# Digital.net
KiCad netlist of a schematic drawn in Altium Designer
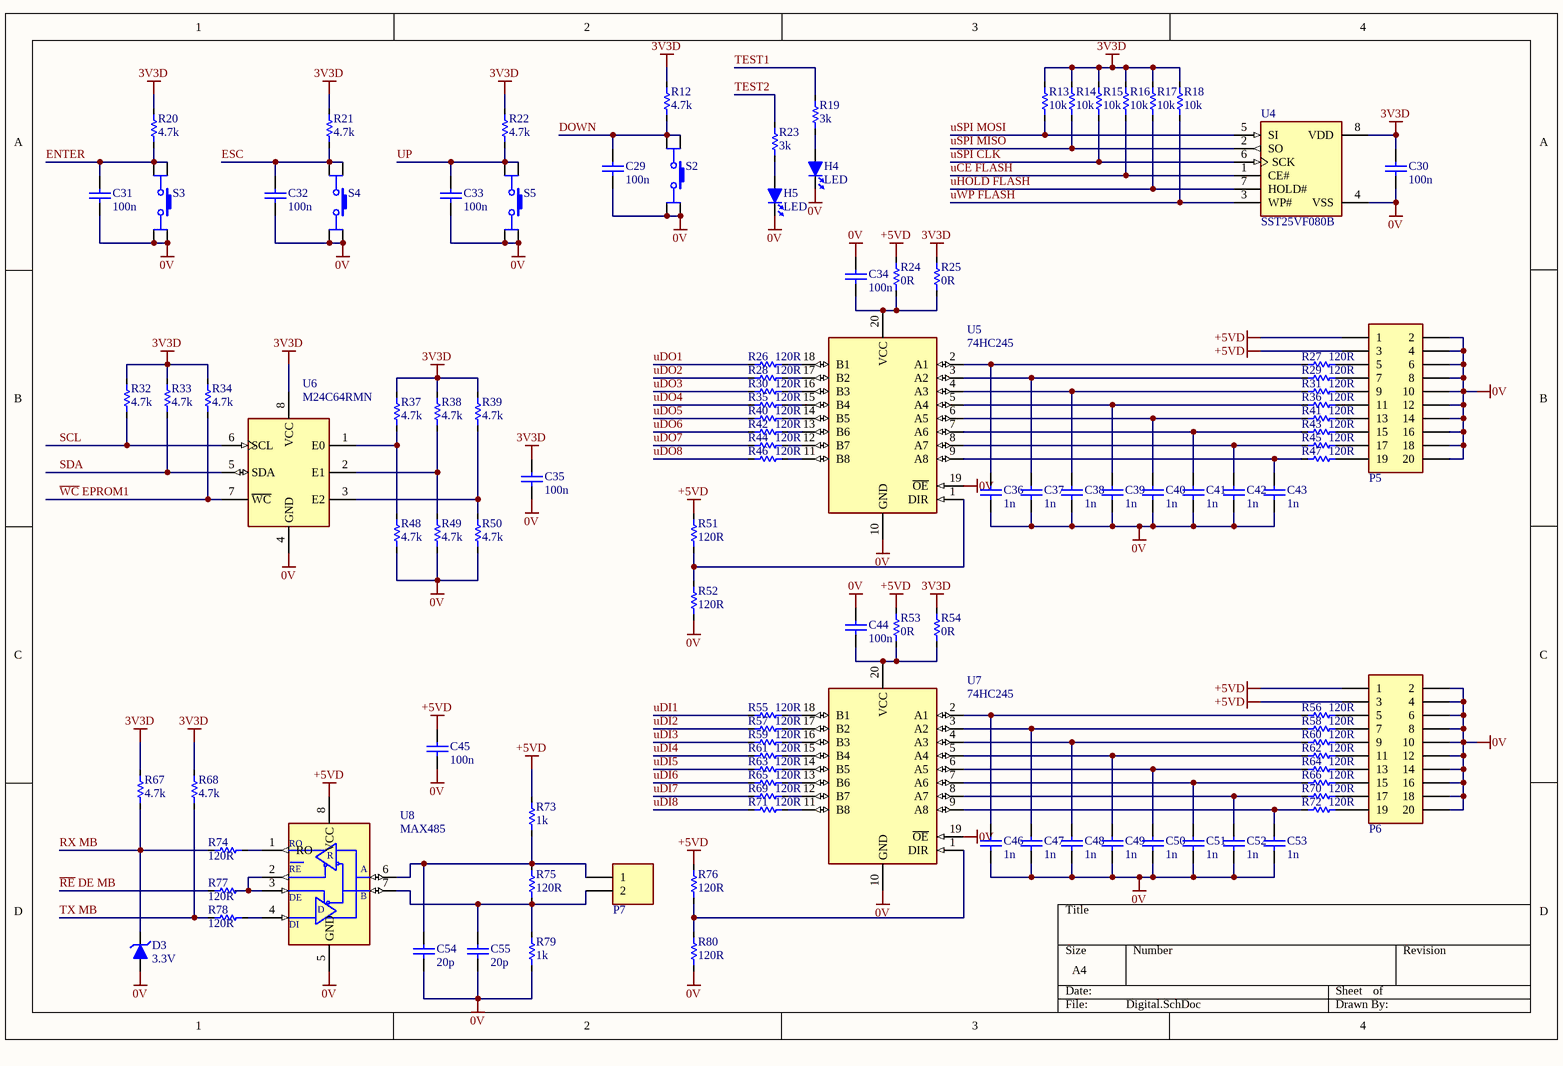
[diagram p0: Digital.SchDoc]

(export (version "E")
  (design (tool "Eeschema 10.0.6"))
  (components
    (comp (ref "C29")
      (value "100n")
      (footprint "CC3216-1206L")
      (description "Capacitor")
      (libsource (lib "SchLibrary") (part "CAPACITOR NON-POL"))
    )
    (comp (ref "C30")
      (value "100n")
      (footprint "CC3216-1206L")
      (description "Capacitor")
      (libsource (lib "SchLibrary") (part "CAPACITOR NON-POL"))
    )
    (comp (ref "C31")
      (value "100n")
      (footprint "CC3216-1206L")
      (description "Capacitor")
      (libsource (lib "SchLibrary") (part "CAPACITOR NON-POL"))
    )
    (comp (ref "C32")
      (value "100n")
      (footprint "CC3216-1206L")
      (description "Capacitor")
      (libsource (lib "SchLibrary") (part "CAPACITOR NON-POL"))
    )
    (comp (ref "C33")
      (value "100n")
      (footprint "CC3216-1206L")
      (description "Capacitor")
      (libsource (lib "SchLibrary") (part "CAPACITOR NON-POL"))
    )
    (comp (ref "C34")
      (value "100n")
      (footprint "CC3216-1206L")
      (description "Capacitor")
      (libsource (lib "SchLibrary") (part "CAPACITOR NON-POL"))
    )
    (comp (ref "C35")
      (value "100n")
      (footprint "CC3216-1206L")
      (description "Capacitor")
      (libsource (lib "SchLibrary") (part "CAPACITOR NON-POL"))
    )
    (comp (ref "C36")
      (value "1n")
      (footprint "CC3216-1206L")
      (description "Capacitor")
      (libsource (lib "SchLibrary") (part "CAPACITOR NON-POL"))
    )
    (comp (ref "C37")
      (value "1n")
      (footprint "CC3216-1206L")
      (description "Capacitor")
      (libsource (lib "SchLibrary") (part "CAPACITOR NON-POL"))
    )
    (comp (ref "C38")
      (value "1n")
      (footprint "CC3216-1206L")
      (description "Capacitor")
      (libsource (lib "SchLibrary") (part "CAPACITOR NON-POL"))
    )
    (comp (ref "C39")
      (value "1n")
      (footprint "CC3216-1206L")
      (description "Capacitor")
      (libsource (lib "SchLibrary") (part "CAPACITOR NON-POL"))
    )
    (comp (ref "C40")
      (value "1n")
      (footprint "CC3216-1206L")
      (description "Capacitor")
      (libsource (lib "SchLibrary") (part "CAPACITOR NON-POL"))
    )
    (comp (ref "C41")
      (value "1n")
      (footprint "CC3216-1206L")
      (description "Capacitor")
      (libsource (lib "SchLibrary") (part "CAPACITOR NON-POL"))
    )
    (comp (ref "C42")
      (value "1n")
      (footprint "CC3216-1206L")
      (description "Capacitor")
      (libsource (lib "SchLibrary") (part "CAPACITOR NON-POL"))
    )
    (comp (ref "C43")
      (value "1n")
      (footprint "CC3216-1206L")
      (description "Capacitor")
      (libsource (lib "SchLibrary") (part "CAPACITOR NON-POL"))
    )
    (comp (ref "C44")
      (value "100n")
      (footprint "CC3216-1206L")
      (description "Capacitor")
      (libsource (lib "SchLibrary") (part "CAPACITOR NON-POL"))
    )
    (comp (ref "C45")
      (value "100n")
      (footprint "CC3216-1206L")
      (description "Capacitor")
      (libsource (lib "SchLibrary") (part "CAPACITOR NON-POL"))
    )
    (comp (ref "C46")
      (value "1n")
      (footprint "CC3216-1206L")
      (description "Capacitor")
      (libsource (lib "SchLibrary") (part "CAPACITOR NON-POL"))
    )
    (comp (ref "C47")
      (value "1n")
      (footprint "CC3216-1206L")
      (description "Capacitor")
      (libsource (lib "SchLibrary") (part "CAPACITOR NON-POL"))
    )
    (comp (ref "C48")
      (value "1n")
      (footprint "CC3216-1206L")
      (description "Capacitor")
      (libsource (lib "SchLibrary") (part "CAPACITOR NON-POL"))
    )
    (comp (ref "C49")
      (value "1n")
      (footprint "CC3216-1206L")
      (description "Capacitor")
      (libsource (lib "SchLibrary") (part "CAPACITOR NON-POL"))
    )
    (comp (ref "C50")
      (value "1n")
      (footprint "CC3216-1206L")
      (description "Capacitor")
      (libsource (lib "SchLibrary") (part "CAPACITOR NON-POL"))
    )
    (comp (ref "C51")
      (value "1n")
      (footprint "CC3216-1206L")
      (description "Capacitor")
      (libsource (lib "SchLibrary") (part "CAPACITOR NON-POL"))
    )
    (comp (ref "C52")
      (value "1n")
      (footprint "CC3216-1206L")
      (description "Capacitor")
      (libsource (lib "SchLibrary") (part "CAPACITOR NON-POL"))
    )
    (comp (ref "C53")
      (value "1n")
      (footprint "CC3216-1206L")
      (description "Capacitor")
      (libsource (lib "SchLibrary") (part "CAPACITOR NON-POL"))
    )
    (comp (ref "C54")
      (value "20p")
      (footprint "CC3216-1206L")
      (description "Capacitor")
      (libsource (lib "SchLibrary") (part "CAPACITOR NON-POL"))
    )
    (comp (ref "C55")
      (value "20p")
      (footprint "CC3216-1206L")
      (description "Capacitor")
      (libsource (lib "SchLibrary") (part "CAPACITOR NON-POL"))
    )
    (comp (ref "D3")
      (value "3.3V")
      (footprint "SOD123")
      (description "DIODE ZENER")
      (libsource (lib "SchLibrary") (part "DIODE ZENER"))
    )
    (comp (ref "H4") (value "LED") (footprint "LED1206") (libsource (lib "SchLibrary") (part "LED")))
    (comp (ref "H5") (value "LED") (footprint "LED1206") (libsource (lib "SchLibrary") (part "LED")))
    (comp (ref "P5")
      (value "CONNECTOR, 2x10, 20P")
      (footprint "HDR_MALE_2X10_20P_2.54MM_180")
      (libsource (lib "SchLibrary") (part "CONNECTOR, 2x10, 20P"))
    )
    (comp (ref "P6")
      (value "CONNECTOR, 2x10, 20P")
      (footprint "HDR_MALE_2X10_20P_2.54MM_180")
      (libsource (lib "SchLibrary") (part "CONNECTOR, 2x10, 20P"))
    )
    (comp (ref "P7")
      (value "CONNECTOR, 1x2, 2P")
      (footprint "DS1070-2MVV6")
      (libsource (lib "SchLibrary") (part "CONNECTOR, 1x2, 2P"))
    )
    (comp (ref "R12")
      (value "4.7k")
      (footprint "CR3216-1206l")
      (description "Resistor")
      (libsource (lib "SchLibrary") (part "RESISTOR"))
    )
    (comp (ref "R13")
      (value "10k")
      (footprint "CR3216-1206l")
      (description "Resistor")
      (libsource (lib "SchLibrary") (part "RESISTOR"))
    )
    (comp (ref "R14")
      (value "10k")
      (footprint "CR3216-1206l")
      (description "Resistor")
      (libsource (lib "SchLibrary") (part "RESISTOR"))
    )
    (comp (ref "R15")
      (value "10k")
      (footprint "CR3216-1206l")
      (description "Resistor")
      (libsource (lib "SchLibrary") (part "RESISTOR"))
    )
    (comp (ref "R16")
      (value "10k")
      (footprint "CR3216-1206l")
      (description "Resistor")
      (libsource (lib "SchLibrary") (part "RESISTOR"))
    )
    (comp (ref "R17")
      (value "10k")
      (footprint "CR3216-1206l")
      (description "Resistor")
      (libsource (lib "SchLibrary") (part "RESISTOR"))
    )
    (comp (ref "R18")
      (value "10k")
      (footprint "CR3216-1206l")
      (description "Resistor")
      (libsource (lib "SchLibrary") (part "RESISTOR"))
    )
    (comp (ref "R19")
      (value "3k")
      (footprint "CR3216-1206l")
      (description "Resistor")
      (libsource (lib "SchLibrary") (part "RESISTOR"))
    )
    (comp (ref "R20")
      (value "4.7k")
      (footprint "CR3216-1206l")
      (description "Resistor")
      (libsource (lib "SchLibrary") (part "RESISTOR"))
    )
    (comp (ref "R21")
      (value "4.7k")
      (footprint "CR3216-1206l")
      (description "Resistor")
      (libsource (lib "SchLibrary") (part "RESISTOR"))
    )
    (comp (ref "R22")
      (value "4.7k")
      (footprint "CR3216-1206l")
      (description "Resistor")
      (libsource (lib "SchLibrary") (part "RESISTOR"))
    )
    (comp (ref "R23")
      (value "3k")
      (footprint "CR3216-1206l")
      (description "Resistor")
      (libsource (lib "SchLibrary") (part "RESISTOR"))
    )
    (comp (ref "R24")
      (value "0R")
      (footprint "CR3216-1206l")
      (description "Resistor")
      (libsource (lib "SchLibrary") (part "RESISTOR"))
    )
    (comp (ref "R25")
      (value "0R")
      (footprint "CR3216-1206l")
      (description "Resistor")
      (libsource (lib "SchLibrary") (part "RESISTOR"))
    )
    (comp (ref "R26")
      (value "120R")
      (footprint "CR3216-1206l")
      (description "Resistor")
      (libsource (lib "SchLibrary") (part "RESISTOR"))
    )
    (comp (ref "R27")
      (value "120R")
      (footprint "CR3216-1206l")
      (description "Resistor")
      (libsource (lib "SchLibrary") (part "RESISTOR"))
    )
    (comp (ref "R28")
      (value "120R")
      (footprint "CR3216-1206l")
      (description "Resistor")
      (libsource (lib "SchLibrary") (part "RESISTOR"))
    )
    (comp (ref "R29")
      (value "120R")
      (footprint "CR3216-1206l")
      (description "Resistor")
      (libsource (lib "SchLibrary") (part "RESISTOR"))
    )
    (comp (ref "R30")
      (value "120R")
      (footprint "CR3216-1206l")
      (description "Resistor")
      (libsource (lib "SchLibrary") (part "RESISTOR"))
    )
    (comp (ref "R31")
      (value "120R")
      (footprint "CR3216-1206l")
      (description "Resistor")
      (libsource (lib "SchLibrary") (part "RESISTOR"))
    )
    (comp (ref "R32")
      (value "4.7k")
      (footprint "CR3216-1206l")
      (description "Resistor")
      (libsource (lib "SchLibrary") (part "RESISTOR"))
    )
    (comp (ref "R33")
      (value "4.7k")
      (footprint "CR3216-1206l")
      (description "Resistor")
      (libsource (lib "SchLibrary") (part "RESISTOR"))
    )
    (comp (ref "R34")
      (value "4.7k")
      (footprint "CR3216-1206l")
      (description "Resistor")
      (libsource (lib "SchLibrary") (part "RESISTOR"))
    )
    (comp (ref "R35")
      (value "120R")
      (footprint "CR3216-1206l")
      (description "Resistor")
      (libsource (lib "SchLibrary") (part "RESISTOR"))
    )
    (comp (ref "R36")
      (value "120R")
      (footprint "CR3216-1206l")
      (description "Resistor")
      (libsource (lib "SchLibrary") (part "RESISTOR"))
    )
    (comp (ref "R37")
      (value "4.7k")
      (footprint "CR3216-1206l")
      (description "Resistor")
      (libsource (lib "SchLibrary") (part "RESISTOR"))
    )
    (comp (ref "R38")
      (value "4.7k")
      (footprint "CR3216-1206l")
      (description "Resistor")
      (libsource (lib "SchLibrary") (part "RESISTOR"))
    )
    (comp (ref "R39")
      (value "4.7k")
      (footprint "CR3216-1206l")
      (description "Resistor")
      (libsource (lib "SchLibrary") (part "RESISTOR"))
    )
    (comp (ref "R40")
      (value "120R")
      (footprint "CR3216-1206l")
      (description "Resistor")
      (libsource (lib "SchLibrary") (part "RESISTOR"))
    )
    (comp (ref "R41")
      (value "120R")
      (footprint "CR3216-1206l")
      (description "Resistor")
      (libsource (lib "SchLibrary") (part "RESISTOR"))
    )
    (comp (ref "R42")
      (value "120R")
      (footprint "CR3216-1206l")
      (description "Resistor")
      (libsource (lib "SchLibrary") (part "RESISTOR"))
    )
    (comp (ref "R43")
      (value "120R")
      (footprint "CR3216-1206l")
      (description "Resistor")
      (libsource (lib "SchLibrary") (part "RESISTOR"))
    )
    (comp (ref "R44")
      (value "120R")
      (footprint "CR3216-1206l")
      (description "Resistor")
      (libsource (lib "SchLibrary") (part "RESISTOR"))
    )
    (comp (ref "R45")
      (value "120R")
      (footprint "CR3216-1206l")
      (description "Resistor")
      (libsource (lib "SchLibrary") (part "RESISTOR"))
    )
    (comp (ref "R46")
      (value "120R")
      (footprint "CR3216-1206l")
      (description "Resistor")
      (libsource (lib "SchLibrary") (part "RESISTOR"))
    )
    (comp (ref "R47")
      (value "120R")
      (footprint "CR3216-1206l")
      (description "Resistor")
      (libsource (lib "SchLibrary") (part "RESISTOR"))
    )
    (comp (ref "R48")
      (value "4.7k")
      (footprint "CR3216-1206l")
      (description "Resistor")
      (libsource (lib "SchLibrary") (part "RESISTOR"))
    )
    (comp (ref "R49")
      (value "4.7k")
      (footprint "CR3216-1206l")
      (description "Resistor")
      (libsource (lib "SchLibrary") (part "RESISTOR"))
    )
    (comp (ref "R50")
      (value "4.7k")
      (footprint "CR3216-1206l")
      (description "Resistor")
      (libsource (lib "SchLibrary") (part "RESISTOR"))
    )
    (comp (ref "R51")
      (value "120R")
      (footprint "CR3216-1206l")
      (description "Resistor")
      (libsource (lib "SchLibrary") (part "RESISTOR"))
    )
    (comp (ref "R52")
      (value "120R")
      (footprint "CR3216-1206l")
      (description "Resistor")
      (libsource (lib "SchLibrary") (part "RESISTOR"))
    )
    (comp (ref "R53")
      (value "0R")
      (footprint "CR3216-1206l")
      (description "Resistor")
      (libsource (lib "SchLibrary") (part "RESISTOR"))
    )
    (comp (ref "R54")
      (value "0R")
      (footprint "CR3216-1206l")
      (description "Resistor")
      (libsource (lib "SchLibrary") (part "RESISTOR"))
    )
    (comp (ref "R55")
      (value "120R")
      (footprint "CR3216-1206l")
      (description "Resistor")
      (libsource (lib "SchLibrary") (part "RESISTOR"))
    )
    (comp (ref "R56")
      (value "120R")
      (footprint "CR3216-1206l")
      (description "Resistor")
      (libsource (lib "SchLibrary") (part "RESISTOR"))
    )
    (comp (ref "R57")
      (value "120R")
      (footprint "CR3216-1206l")
      (description "Resistor")
      (libsource (lib "SchLibrary") (part "RESISTOR"))
    )
    (comp (ref "R58")
      (value "120R")
      (footprint "CR3216-1206l")
      (description "Resistor")
      (libsource (lib "SchLibrary") (part "RESISTOR"))
    )
    (comp (ref "R59")
      (value "120R")
      (footprint "CR3216-1206l")
      (description "Resistor")
      (libsource (lib "SchLibrary") (part "RESISTOR"))
    )
    (comp (ref "R60")
      (value "120R")
      (footprint "CR3216-1206l")
      (description "Resistor")
      (libsource (lib "SchLibrary") (part "RESISTOR"))
    )
    (comp (ref "R61")
      (value "120R")
      (footprint "CR3216-1206l")
      (description "Resistor")
      (libsource (lib "SchLibrary") (part "RESISTOR"))
    )
    (comp (ref "R62")
      (value "120R")
      (footprint "CR3216-1206l")
      (description "Resistor")
      (libsource (lib "SchLibrary") (part "RESISTOR"))
    )
    (comp (ref "R63")
      (value "120R")
      (footprint "CR3216-1206l")
      (description "Resistor")
      (libsource (lib "SchLibrary") (part "RESISTOR"))
    )
    (comp (ref "R64")
      (value "120R")
      (footprint "CR3216-1206l")
      (description "Resistor")
      (libsource (lib "SchLibrary") (part "RESISTOR"))
    )
    (comp (ref "R65")
      (value "120R")
      (footprint "CR3216-1206l")
      (description "Resistor")
      (libsource (lib "SchLibrary") (part "RESISTOR"))
    )
    (comp (ref "R66")
      (value "120R")
      (footprint "CR3216-1206l")
      (description "Resistor")
      (libsource (lib "SchLibrary") (part "RESISTOR"))
    )
    (comp (ref "R67")
      (value "4.7k")
      (footprint "CR3216-1206l")
      (description "Resistor")
      (libsource (lib "SchLibrary") (part "RESISTOR"))
    )
    (comp (ref "R68")
      (value "4.7k")
      (footprint "CR3216-1206l")
      (description "Resistor")
      (libsource (lib "SchLibrary") (part "RESISTOR"))
    )
    (comp (ref "R69")
      (value "120R")
      (footprint "CR3216-1206l")
      (description "Resistor")
      (libsource (lib "SchLibrary") (part "RESISTOR"))
    )
    (comp (ref "R70")
      (value "120R")
      (footprint "CR3216-1206l")
      (description "Resistor")
      (libsource (lib "SchLibrary") (part "RESISTOR"))
    )
    (comp (ref "R71")
      (value "120R")
      (footprint "CR3216-1206l")
      (description "Resistor")
      (libsource (lib "SchLibrary") (part "RESISTOR"))
    )
    (comp (ref "R72")
      (value "120R")
      (footprint "CR3216-1206l")
      (description "Resistor")
      (libsource (lib "SchLibrary") (part "RESISTOR"))
    )
    (comp (ref "R73")
      (value "1k")
      (footprint "CR3216-1206l")
      (description "Resistor")
      (libsource (lib "SchLibrary") (part "RESISTOR"))
    )
    (comp (ref "R74")
      (value "120R")
      (footprint "CR3216-1206l")
      (description "Resistor")
      (libsource (lib "SchLibrary") (part "RESISTOR"))
    )
    (comp (ref "R75")
      (value "120R")
      (footprint "CR3216-1206l")
      (description "Resistor")
      (libsource (lib "SchLibrary") (part "RESISTOR"))
    )
    (comp (ref "R76")
      (value "120R")
      (footprint "CR3216-1206l")
      (description "Resistor")
      (libsource (lib "SchLibrary") (part "RESISTOR"))
    )
    (comp (ref "R77")
      (value "120R")
      (footprint "CR3216-1206l")
      (description "Resistor")
      (libsource (lib "SchLibrary") (part "RESISTOR"))
    )
    (comp (ref "R78")
      (value "120R")
      (footprint "CR3216-1206l")
      (description "Resistor")
      (libsource (lib "SchLibrary") (part "RESISTOR"))
    )
    (comp (ref "R79")
      (value "1k")
      (footprint "CR3216-1206l")
      (description "Resistor")
      (libsource (lib "SchLibrary") (part "RESISTOR"))
    )
    (comp (ref "R80")
      (value "120R")
      (footprint "CR3216-1206l")
      (description "Resistor")
      (libsource (lib "SchLibrary") (part "RESISTOR"))
    )
    (comp (ref "S2")
      (value "SWITCH TACT")
      (footprint "SWITCH TACTILE SMD 6x6 4.3mm")
      (description "TACT SWITCH")
      (libsource (lib "SchLibrary") (part "SWITCH TACT"))
    )
    (comp (ref "S3")
      (value "SWITCH TACT")
      (footprint "SWITCH TACTILE SMD 6x6 4.3mm")
      (description "TACT SWITCH")
      (libsource (lib "SchLibrary") (part "SWITCH TACT"))
    )
    (comp (ref "S4")
      (value "SWITCH TACT")
      (footprint "SWITCH TACTILE SMD 6x6 4.3mm")
      (description "TACT SWITCH")
      (libsource (lib "SchLibrary") (part "SWITCH TACT"))
    )
    (comp (ref "S5")
      (value "SWITCH TACT")
      (footprint "SWITCH TACTILE SMD 6x6 4.3mm")
      (description "TACT SWITCH")
      (libsource (lib "SchLibrary") (part "SWITCH TACT"))
    )
    (comp (ref "U4")
      (value "SST25VF080B")
      (footprint "SOIC08-S2A")
      (libsource (lib "SchLibrary") (part "SST25VF080B"))
    )
    (comp (ref "U5")
      (value "74HC245")
      (footprint "SOIC127P1030X265-20M")
      (description "IC BUS TRANSCEIVER 8BIT 20-Pin")
      (libsource (lib "SchLibrary") (part "74HC245"))
    )
    (comp (ref "U6")
      (value "M24C64RMN")
      (footprint "SOIC127P600X175-8N")
      (libsource (lib "SchLibrary") (part "M24C64RMN"))
    )
    (comp (ref "U7")
      (value "74HC245")
      (footprint "SOIC127P1030X265-20M")
      (description "IC BUS TRANSCEIVER 8BIT 20-Pin")
      (libsource (lib "SchLibrary") (part "74HC245"))
    )
    (comp (ref "U8")
      (value "MAX485")
      (footprint "SOIC127P600X175-8N")
      (description "ROHS-ICMAX485CSA MAXIM")
      (libsource (lib "SchLibrary") (part "MAX485"))
    )
  )
  (nets
    (net (code "1") (name "+5VD") (class "Default")
      (node (ref "C45") (pin "1") (pintype "passive"))
      (node (ref "P5") (pin "1") (pinfunction "1_1") (pintype "passive"))
      (node (ref "P5") (pin "3") (pinfunction "3_3") (pintype "passive"))
      (node (ref "P6") (pin "1") (pinfunction "1_1") (pintype "passive"))
      (node (ref "P6") (pin "3") (pinfunction "3_3") (pintype "passive"))
      (node (ref "R24") (pin "1") (pinfunction "1_1") (pintype "passive"))
      (node (ref "R51") (pin "1") (pinfunction "1_1") (pintype "passive"))
      (node (ref "R53") (pin "1") (pinfunction "1_1") (pintype "passive"))
      (node (ref "R73") (pin "1") (pinfunction "1_1") (pintype "passive"))
      (node (ref "R76") (pin "1") (pinfunction "1_1") (pintype "passive"))
      (node (ref "U8") (pin "8") (pinfunction "VCC_8") (pintype "power_in"))
    )
    (net (code "2") (name "/DOWN") (class "Default")
      (node (ref "C29") (pin "1") (pintype "passive"))
      (node (ref "R12") (pin "2") (pinfunction "2_2") (pintype "passive"))
      (node (ref "S2") (pin "1") (pinfunction "A_1") (pintype "passive"))
      (node (ref "S2") (pin "2") (pinfunction "A_2") (pintype "passive"))
    )
    (net (code "3") (name "/ENTER") (class "Default")
      (node (ref "C31") (pin "1") (pintype "passive"))
      (node (ref "R20") (pin "2") (pinfunction "2_2") (pintype "passive"))
      (node (ref "S3") (pin "1") (pinfunction "A_1") (pintype "passive"))
      (node (ref "S3") (pin "2") (pinfunction "A_2") (pintype "passive"))
    )
    (net (code "4") (name "/ESC") (class "Default")
      (node (ref "C32") (pin "1") (pintype "passive"))
      (node (ref "R21") (pin "2") (pinfunction "2_2") (pintype "passive"))
      (node (ref "S4") (pin "1") (pinfunction "A_1") (pintype "passive"))
      (node (ref "S4") (pin "2") (pinfunction "A_2") (pintype "passive"))
    )
    (net (code "5") (name "/RX MB") (class "Default")
      (node (ref "D3") (pin "2") (pinfunction "2_2") (pintype "passive"))
      (node (ref "R67") (pin "2") (pinfunction "2_2") (pintype "passive"))
      (node (ref "R74") (pin "2") (pinfunction "2_2") (pintype "passive"))
    )
    (net (code "6") (name "/SCL") (class "Default")
      (node (ref "R32") (pin "2") (pinfunction "2_2") (pintype "passive"))
      (node (ref "U6") (pin "6") (pinfunction "SCL_6") (pintype "input"))
    )
    (net (code "7") (name "/SDA") (class "Default")
      (node (ref "R33") (pin "2") (pinfunction "2_2") (pintype "passive"))
      (node (ref "U6") (pin "5") (pinfunction "SDA_5") (pintype "bidirectional"))
    )
    (net (code "8") (name "/TEST1") (class "Default")
      (node (ref "R19") (pin "2") (pinfunction "2_2") (pintype "passive"))
    )
    (net (code "9") (name "/TEST2") (class "Default")
      (node (ref "R23") (pin "2") (pinfunction "2_2") (pintype "passive"))
    )
    (net (code "10") (name "/TX MB") (class "Default")
      (node (ref "R68") (pin "2") (pinfunction "2_2") (pintype "passive"))
      (node (ref "R78") (pin "2") (pinfunction "2_2") (pintype "passive"))
    )
    (net (code "11") (name "/UP") (class "Default")
      (node (ref "C33") (pin "1") (pintype "passive"))
      (node (ref "R22") (pin "2") (pinfunction "2_2") (pintype "passive"))
      (node (ref "S5") (pin "1") (pinfunction "A_1") (pintype "passive"))
      (node (ref "S5") (pin "2") (pinfunction "A_2") (pintype "passive"))
    )
    (net (code "12") (name "/uCE FLASH") (class "Default")
      (node (ref "R16") (pin "1") (pinfunction "1_1") (pintype "passive"))
      (node (ref "U4") (pin "1") (pinfunction "CE#_1") (pintype "passive"))
    )
    (net (code "13") (name "/uDI1") (class "Default")
      (node (ref "R55") (pin "1") (pinfunction "1_1") (pintype "passive"))
    )
    (net (code "14") (name "/uDI2") (class "Default")
      (node (ref "R57") (pin "1") (pinfunction "1_1") (pintype "passive"))
    )
    (net (code "15") (name "/uDI3") (class "Default")
      (node (ref "R59") (pin "1") (pinfunction "1_1") (pintype "passive"))
    )
    (net (code "16") (name "/uDI4") (class "Default")
      (node (ref "R61") (pin "1") (pinfunction "1_1") (pintype "passive"))
    )
    (net (code "17") (name "/uDI5") (class "Default")
      (node (ref "R63") (pin "1") (pinfunction "1_1") (pintype "passive"))
    )
    (net (code "18") (name "/uDI6") (class "Default")
      (node (ref "R65") (pin "1") (pinfunction "1_1") (pintype "passive"))
    )
    (net (code "19") (name "/uDI7") (class "Default")
      (node (ref "R69") (pin "1") (pinfunction "1_1") (pintype "passive"))
    )
    (net (code "20") (name "/uDI8") (class "Default")
      (node (ref "R71") (pin "1") (pinfunction "1_1") (pintype "passive"))
    )
    (net (code "21") (name "/uDO1") (class "Default")
      (node (ref "R26") (pin "1") (pinfunction "1_1") (pintype "passive"))
    )
    (net (code "22") (name "/uDO2") (class "Default")
      (node (ref "R28") (pin "1") (pinfunction "1_1") (pintype "passive"))
    )
    (net (code "23") (name "/uDO3") (class "Default")
      (node (ref "R30") (pin "1") (pinfunction "1_1") (pintype "passive"))
    )
    (net (code "24") (name "/uDO4") (class "Default")
      (node (ref "R35") (pin "1") (pinfunction "1_1") (pintype "passive"))
    )
    (net (code "25") (name "/uDO5") (class "Default")
      (node (ref "R40") (pin "1") (pinfunction "1_1") (pintype "passive"))
    )
    (net (code "26") (name "/uDO6") (class "Default")
      (node (ref "R42") (pin "1") (pinfunction "1_1") (pintype "passive"))
    )
    (net (code "27") (name "/uDO7") (class "Default")
      (node (ref "R44") (pin "1") (pinfunction "1_1") (pintype "passive"))
    )
    (net (code "28") (name "/uDO8") (class "Default")
      (node (ref "R46") (pin "1") (pinfunction "1_1") (pintype "passive"))
    )
    (net (code "29") (name "/uHOLD FLASH") (class "Default")
      (node (ref "R17") (pin "1") (pinfunction "1_1") (pintype "passive"))
      (node (ref "U4") (pin "7") (pinfunction "HOLD#_7") (pintype "passive"))
    )
    (net (code "30") (name "/uSPI CLK") (class "Default")
      (node (ref "R15") (pin "1") (pinfunction "1_1") (pintype "passive"))
      (node (ref "U4") (pin "6") (pinfunction "SCK_6") (pintype "input"))
    )
    (net (code "31") (name "/uSPI MISO") (class "Default")
      (node (ref "R14") (pin "1") (pinfunction "1_1") (pintype "passive"))
      (node (ref "U4") (pin "2") (pinfunction "SO_2") (pintype "output"))
    )
    (net (code "32") (name "/uSPI MOSI") (class "Default")
      (node (ref "R13") (pin "1") (pinfunction "1_1") (pintype "passive"))
      (node (ref "U4") (pin "5") (pinfunction "SI_5") (pintype "input"))
    )
    (net (code "33") (name "/uWP FLASH") (class "Default")
      (node (ref "R18") (pin "1") (pinfunction "1_1") (pintype "passive"))
      (node (ref "U4") (pin "3") (pinfunction "WP#_3") (pintype "passive"))
    )
    (net (code "34") (name "/~{RE} DE MB") (class "Default")
      (node (ref "R77") (pin "2") (pinfunction "2_2") (pintype "passive"))
    )
    (net (code "35") (name "/~{WC} EPROM1") (class "Default")
      (node (ref "R34") (pin "2") (pinfunction "2_2") (pintype "passive"))
      (node (ref "U6") (pin "7") (pinfunction "~{WC}_7") (pintype "passive"))
    )
    (net (code "36") (name "0V") (class "Default")
      (node (ref "C29") (pin "2") (pintype "passive"))
      (node (ref "C30") (pin "2") (pintype "passive"))
      (node (ref "C31") (pin "2") (pintype "passive"))
      (node (ref "C32") (pin "2") (pintype "passive"))
      (node (ref "C33") (pin "2") (pintype "passive"))
      (node (ref "C34") (pin "1") (pintype "passive"))
      (node (ref "C35") (pin "2") (pintype "passive"))
      (node (ref "C36") (pin "2") (pintype "passive"))
      (node (ref "C37") (pin "2") (pintype "passive"))
      (node (ref "C38") (pin "2") (pintype "passive"))
      (node (ref "C39") (pin "2") (pintype "passive"))
      (node (ref "C40") (pin "2") (pintype "passive"))
      (node (ref "C41") (pin "2") (pintype "passive"))
      (node (ref "C42") (pin "2") (pintype "passive"))
      (node (ref "C43") (pin "2") (pintype "passive"))
      (node (ref "C44") (pin "1") (pintype "passive"))
      (node (ref "C45") (pin "2") (pintype "passive"))
      (node (ref "C46") (pin "2") (pintype "passive"))
      (node (ref "C47") (pin "2") (pintype "passive"))
      (node (ref "C48") (pin "2") (pintype "passive"))
      (node (ref "C49") (pin "2") (pintype "passive"))
      (node (ref "C50") (pin "2") (pintype "passive"))
      (node (ref "C51") (pin "2") (pintype "passive"))
      (node (ref "C52") (pin "2") (pintype "passive"))
      (node (ref "C53") (pin "2") (pintype "passive"))
      (node (ref "C54") (pin "2") (pintype "passive"))
      (node (ref "C55") (pin "2") (pintype "passive"))
      (node (ref "D3") (pin "1") (pinfunction "1_1") (pintype "passive"))
      (node (ref "H4") (pin "2") (pinfunction "CATHODE_2") (pintype "passive"))
      (node (ref "H5") (pin "2") (pinfunction "CATHODE_2") (pintype "passive"))
      (node (ref "P5") (pin "10") (pinfunction "10_10") (pintype "passive"))
      (node (ref "P5") (pin "12") (pinfunction "12_12") (pintype "passive"))
      (node (ref "P5") (pin "14") (pinfunction "14_14") (pintype "passive"))
      (node (ref "P5") (pin "16") (pinfunction "16_16") (pintype "passive"))
      (node (ref "P5") (pin "18") (pinfunction "18_18") (pintype "passive"))
      (node (ref "P5") (pin "2") (pinfunction "2_2") (pintype "passive"))
      (node (ref "P5") (pin "20") (pinfunction "20_20") (pintype "passive"))
      (node (ref "P5") (pin "4") (pinfunction "4_4") (pintype "passive"))
      (node (ref "P5") (pin "6") (pinfunction "6_6") (pintype "passive"))
      (node (ref "P5") (pin "8") (pinfunction "8_8") (pintype "passive"))
      (node (ref "P6") (pin "10") (pinfunction "10_10") (pintype "passive"))
      (node (ref "P6") (pin "12") (pinfunction "12_12") (pintype "passive"))
      (node (ref "P6") (pin "14") (pinfunction "14_14") (pintype "passive"))
      (node (ref "P6") (pin "16") (pinfunction "16_16") (pintype "passive"))
      (node (ref "P6") (pin "18") (pinfunction "18_18") (pintype "passive"))
      (node (ref "P6") (pin "2") (pinfunction "2_2") (pintype "passive"))
      (node (ref "P6") (pin "20") (pinfunction "20_20") (pintype "passive"))
      (node (ref "P6") (pin "4") (pinfunction "4_4") (pintype "passive"))
      (node (ref "P6") (pin "6") (pinfunction "6_6") (pintype "passive"))
      (node (ref "P6") (pin "8") (pinfunction "8_8") (pintype "passive"))
      (node (ref "R48") (pin "2") (pinfunction "2_2") (pintype "passive"))
      (node (ref "R49") (pin "2") (pinfunction "2_2") (pintype "passive"))
      (node (ref "R50") (pin "2") (pinfunction "2_2") (pintype "passive"))
      (node (ref "R52") (pin "2") (pinfunction "2_2") (pintype "passive"))
      (node (ref "R79") (pin "2") (pinfunction "2_2") (pintype "passive"))
      (node (ref "R80") (pin "2") (pinfunction "2_2") (pintype "passive"))
      (node (ref "S2") (pin "3") (pinfunction "B_3") (pintype "passive"))
      (node (ref "S2") (pin "4") (pinfunction "B_4") (pintype "passive"))
      (node (ref "S3") (pin "3") (pinfunction "B_3") (pintype "passive"))
      (node (ref "S3") (pin "4") (pinfunction "B_4") (pintype "passive"))
      (node (ref "S4") (pin "3") (pinfunction "B_3") (pintype "passive"))
      (node (ref "S4") (pin "4") (pinfunction "B_4") (pintype "passive"))
      (node (ref "S5") (pin "3") (pinfunction "B_3") (pintype "passive"))
      (node (ref "S5") (pin "4") (pinfunction "B_4") (pintype "passive"))
      (node (ref "U4") (pin "4") (pinfunction "VSS_4") (pintype "power_in"))
      (node (ref "U5") (pin "10") (pinfunction "GND_10") (pintype "power_in"))
      (node (ref "U5") (pin "19") (pinfunction "~{OE}_19") (pintype "input"))
      (node (ref "U6") (pin "4") (pinfunction "GND_4") (pintype "power_in"))
      (node (ref "U7") (pin "10") (pinfunction "GND_10") (pintype "power_in"))
      (node (ref "U7") (pin "19") (pinfunction "~{OE}_19") (pintype "input"))
      (node (ref "U8") (pin "5") (pinfunction "GND_5") (pintype "power_in"))
    )
    (net (code "37") (name "3V3D") (class "Default")
      (node (ref "C30") (pin "1") (pintype "passive"))
      (node (ref "C35") (pin "1") (pintype "passive"))
      (node (ref "R12") (pin "1") (pinfunction "1_1") (pintype "passive"))
      (node (ref "R13") (pin "2") (pinfunction "2_2") (pintype "passive"))
      (node (ref "R14") (pin "2") (pinfunction "2_2") (pintype "passive"))
      (node (ref "R15") (pin "2") (pinfunction "2_2") (pintype "passive"))
      (node (ref "R16") (pin "2") (pinfunction "2_2") (pintype "passive"))
      (node (ref "R17") (pin "2") (pinfunction "2_2") (pintype "passive"))
      (node (ref "R18") (pin "2") (pinfunction "2_2") (pintype "passive"))
      (node (ref "R20") (pin "1") (pinfunction "1_1") (pintype "passive"))
      (node (ref "R21") (pin "1") (pinfunction "1_1") (pintype "passive"))
      (node (ref "R22") (pin "1") (pinfunction "1_1") (pintype "passive"))
      (node (ref "R25") (pin "1") (pinfunction "1_1") (pintype "passive"))
      (node (ref "R32") (pin "1") (pinfunction "1_1") (pintype "passive"))
      (node (ref "R33") (pin "1") (pinfunction "1_1") (pintype "passive"))
      (node (ref "R34") (pin "1") (pinfunction "1_1") (pintype "passive"))
      (node (ref "R37") (pin "1") (pinfunction "1_1") (pintype "passive"))
      (node (ref "R38") (pin "1") (pinfunction "1_1") (pintype "passive"))
      (node (ref "R39") (pin "1") (pinfunction "1_1") (pintype "passive"))
      (node (ref "R54") (pin "1") (pinfunction "1_1") (pintype "passive"))
      (node (ref "R67") (pin "1") (pinfunction "1_1") (pintype "passive"))
      (node (ref "R68") (pin "1") (pinfunction "1_1") (pintype "passive"))
      (node (ref "U4") (pin "8") (pinfunction "VDD_8") (pintype "power_in"))
      (node (ref "U6") (pin "8") (pinfunction "VCC_8") (pintype "power_in"))
    )
    (net (code "38") (name "Net-(H4-ANODE)") (class "Default")
      (node (ref "H4") (pin "1") (pinfunction "ANODE_1") (pintype "passive"))
      (node (ref "R19") (pin "1") (pinfunction "1_1") (pintype "passive"))
    )
    (net (code "39") (name "Net-(H5-ANODE)") (class "Default")
      (node (ref "H5") (pin "1") (pinfunction "ANODE_1") (pintype "passive"))
      (node (ref "R23") (pin "1") (pinfunction "1_1") (pintype "passive"))
    )
    (net (code "40") (name "Net-(P5-Pad5)") (class "Default")
      (node (ref "P5") (pin "5") (pinfunction "5_5") (pintype "passive"))
      (node (ref "R27") (pin "2") (pinfunction "2_2") (pintype "passive"))
    )
    (net (code "41") (name "Net-(P5-Pad7)") (class "Default")
      (node (ref "P5") (pin "7") (pinfunction "7_7") (pintype "passive"))
      (node (ref "R29") (pin "2") (pinfunction "2_2") (pintype "passive"))
    )
    (net (code "42") (name "Net-(P5-Pad9)") (class "Default")
      (node (ref "P5") (pin "9") (pinfunction "9_9") (pintype "passive"))
      (node (ref "R31") (pin "2") (pinfunction "2_2") (pintype "passive"))
    )
    (net (code "43") (name "Net-(P5-Pad11)") (class "Default")
      (node (ref "P5") (pin "11") (pinfunction "11_11") (pintype "passive"))
      (node (ref "R36") (pin "2") (pinfunction "2_2") (pintype "passive"))
    )
    (net (code "44") (name "Net-(P5-Pad13)") (class "Default")
      (node (ref "P5") (pin "13") (pinfunction "13_13") (pintype "passive"))
      (node (ref "R41") (pin "2") (pinfunction "2_2") (pintype "passive"))
    )
    (net (code "45") (name "Net-(P5-Pad15)") (class "Default")
      (node (ref "P5") (pin "15") (pinfunction "15_15") (pintype "passive"))
      (node (ref "R43") (pin "2") (pinfunction "2_2") (pintype "passive"))
    )
    (net (code "46") (name "Net-(P5-Pad17)") (class "Default")
      (node (ref "P5") (pin "17") (pinfunction "17_17") (pintype "passive"))
      (node (ref "R45") (pin "2") (pinfunction "2_2") (pintype "passive"))
    )
    (net (code "47") (name "Net-(P5-Pad19)") (class "Default")
      (node (ref "P5") (pin "19") (pinfunction "19_19") (pintype "passive"))
      (node (ref "R47") (pin "2") (pinfunction "2_2") (pintype "passive"))
    )
    (net (code "48") (name "Net-(P6-Pad5)") (class "Default")
      (node (ref "P6") (pin "5") (pinfunction "5_5") (pintype "passive"))
      (node (ref "R56") (pin "2") (pinfunction "2_2") (pintype "passive"))
    )
    (net (code "49") (name "Net-(P6-Pad7)") (class "Default")
      (node (ref "P6") (pin "7") (pinfunction "7_7") (pintype "passive"))
      (node (ref "R58") (pin "2") (pinfunction "2_2") (pintype "passive"))
    )
    (net (code "50") (name "Net-(P6-Pad9)") (class "Default")
      (node (ref "P6") (pin "9") (pinfunction "9_9") (pintype "passive"))
      (node (ref "R60") (pin "2") (pinfunction "2_2") (pintype "passive"))
    )
    (net (code "51") (name "Net-(P6-Pad11)") (class "Default")
      (node (ref "P6") (pin "11") (pinfunction "11_11") (pintype "passive"))
      (node (ref "R62") (pin "2") (pinfunction "2_2") (pintype "passive"))
    )
    (net (code "52") (name "Net-(P6-Pad13)") (class "Default")
      (node (ref "P6") (pin "13") (pinfunction "13_13") (pintype "passive"))
      (node (ref "R64") (pin "2") (pinfunction "2_2") (pintype "passive"))
    )
    (net (code "53") (name "Net-(P6-Pad15)") (class "Default")
      (node (ref "P6") (pin "15") (pinfunction "15_15") (pintype "passive"))
      (node (ref "R66") (pin "2") (pinfunction "2_2") (pintype "passive"))
    )
    (net (code "54") (name "Net-(P6-Pad17)") (class "Default")
      (node (ref "P6") (pin "17") (pinfunction "17_17") (pintype "passive"))
      (node (ref "R70") (pin "2") (pinfunction "2_2") (pintype "passive"))
    )
    (net (code "55") (name "Net-(P6-Pad19)") (class "Default")
      (node (ref "P6") (pin "19") (pinfunction "19_19") (pintype "passive"))
      (node (ref "R72") (pin "2") (pinfunction "2_2") (pintype "passive"))
    )
    (net (code "56") (name "Net-(U5-A1)") (class "Default")
      (node (ref "C36") (pin "1") (pintype "passive"))
      (node (ref "R27") (pin "1") (pinfunction "1_1") (pintype "passive"))
      (node (ref "U5") (pin "2") (pinfunction "A1_2") (pintype "bidirectional"))
    )
    (net (code "57") (name "Net-(U5-A2)") (class "Default")
      (node (ref "C37") (pin "1") (pintype "passive"))
      (node (ref "R29") (pin "1") (pinfunction "1_1") (pintype "passive"))
      (node (ref "U5") (pin "3") (pinfunction "A2_3") (pintype "bidirectional"))
    )
    (net (code "58") (name "Net-(U5-A3)") (class "Default")
      (node (ref "C38") (pin "1") (pintype "passive"))
      (node (ref "R31") (pin "1") (pinfunction "1_1") (pintype "passive"))
      (node (ref "U5") (pin "4") (pinfunction "A3_4") (pintype "bidirectional"))
    )
    (net (code "59") (name "Net-(U5-A4)") (class "Default")
      (node (ref "C39") (pin "1") (pintype "passive"))
      (node (ref "R36") (pin "1") (pinfunction "1_1") (pintype "passive"))
      (node (ref "U5") (pin "5") (pinfunction "A4_5") (pintype "bidirectional"))
    )
    (net (code "60") (name "Net-(U5-A5)") (class "Default")
      (node (ref "C40") (pin "1") (pintype "passive"))
      (node (ref "R41") (pin "1") (pinfunction "1_1") (pintype "passive"))
      (node (ref "U5") (pin "6") (pinfunction "A5_6") (pintype "bidirectional"))
    )
    (net (code "61") (name "Net-(U5-A6)") (class "Default")
      (node (ref "C41") (pin "1") (pintype "passive"))
      (node (ref "R43") (pin "1") (pinfunction "1_1") (pintype "passive"))
      (node (ref "U5") (pin "7") (pinfunction "A6_7") (pintype "bidirectional"))
    )
    (net (code "62") (name "Net-(U5-A7)") (class "Default")
      (node (ref "C42") (pin "1") (pintype "passive"))
      (node (ref "R45") (pin "1") (pinfunction "1_1") (pintype "passive"))
      (node (ref "U5") (pin "8") (pinfunction "A7_8") (pintype "bidirectional"))
    )
    (net (code "63") (name "Net-(U5-A8)") (class "Default")
      (node (ref "C43") (pin "1") (pintype "passive"))
      (node (ref "R47") (pin "1") (pinfunction "1_1") (pintype "passive"))
      (node (ref "U5") (pin "9") (pinfunction "A8_9") (pintype "bidirectional"))
    )
    (net (code "64") (name "Net-(U5-B1)") (class "Default")
      (node (ref "R26") (pin "2") (pinfunction "2_2") (pintype "passive"))
      (node (ref "U5") (pin "18") (pinfunction "B1_18") (pintype "bidirectional"))
    )
    (net (code "65") (name "Net-(U5-B2)") (class "Default")
      (node (ref "R28") (pin "2") (pinfunction "2_2") (pintype "passive"))
      (node (ref "U5") (pin "17") (pinfunction "B2_17") (pintype "bidirectional"))
    )
    (net (code "66") (name "Net-(U5-B3)") (class "Default")
      (node (ref "R30") (pin "2") (pinfunction "2_2") (pintype "passive"))
      (node (ref "U5") (pin "16") (pinfunction "B3_16") (pintype "bidirectional"))
    )
    (net (code "67") (name "Net-(U5-B4)") (class "Default")
      (node (ref "R35") (pin "2") (pinfunction "2_2") (pintype "passive"))
      (node (ref "U5") (pin "15") (pinfunction "B4_15") (pintype "bidirectional"))
    )
    (net (code "68") (name "Net-(U5-B5)") (class "Default")
      (node (ref "R40") (pin "2") (pinfunction "2_2") (pintype "passive"))
      (node (ref "U5") (pin "14") (pinfunction "B5_14") (pintype "bidirectional"))
    )
    (net (code "69") (name "Net-(U5-B6)") (class "Default")
      (node (ref "R42") (pin "2") (pinfunction "2_2") (pintype "passive"))
      (node (ref "U5") (pin "13") (pinfunction "B6_13") (pintype "bidirectional"))
    )
    (net (code "70") (name "Net-(U5-B7)") (class "Default")
      (node (ref "R44") (pin "2") (pinfunction "2_2") (pintype "passive"))
      (node (ref "U5") (pin "12") (pinfunction "B7_12") (pintype "bidirectional"))
    )
    (net (code "71") (name "Net-(U5-B8)") (class "Default")
      (node (ref "R46") (pin "2") (pinfunction "2_2") (pintype "passive"))
      (node (ref "U5") (pin "11") (pinfunction "B8_11") (pintype "bidirectional"))
    )
    (net (code "72") (name "Net-(U5-DIR)") (class "Default")
      (node (ref "R51") (pin "2") (pinfunction "2_2") (pintype "passive"))
      (node (ref "R52") (pin "1") (pinfunction "1_1") (pintype "passive"))
      (node (ref "U5") (pin "1") (pinfunction "DIR_1") (pintype "input"))
    )
    (net (code "73") (name "Net-(U5-VCC)") (class "Default")
      (node (ref "C34") (pin "2") (pintype "passive"))
      (node (ref "R24") (pin "2") (pinfunction "2_2") (pintype "passive"))
      (node (ref "R25") (pin "2") (pinfunction "2_2") (pintype "passive"))
      (node (ref "U5") (pin "20") (pinfunction "VCC_20") (pintype "power_in"))
    )
    (net (code "74") (name "Net-(U6-E0)") (class "Default")
      (node (ref "R37") (pin "2") (pinfunction "2_2") (pintype "passive"))
      (node (ref "R48") (pin "1") (pinfunction "1_1") (pintype "passive"))
      (node (ref "U6") (pin "1") (pinfunction "E0_1") (pintype "passive"))
    )
    (net (code "75") (name "Net-(U6-E1)") (class "Default")
      (node (ref "R38") (pin "2") (pinfunction "2_2") (pintype "passive"))
      (node (ref "R49") (pin "1") (pinfunction "1_1") (pintype "passive"))
      (node (ref "U6") (pin "2") (pinfunction "E1_2") (pintype "passive"))
    )
    (net (code "76") (name "Net-(U6-E2)") (class "Default")
      (node (ref "R39") (pin "2") (pinfunction "2_2") (pintype "passive"))
      (node (ref "R50") (pin "1") (pinfunction "1_1") (pintype "passive"))
      (node (ref "U6") (pin "3") (pinfunction "E2_3") (pintype "passive"))
    )
    (net (code "77") (name "Net-(U7-A1)") (class "Default")
      (node (ref "C46") (pin "1") (pintype "passive"))
      (node (ref "R56") (pin "1") (pinfunction "1_1") (pintype "passive"))
      (node (ref "U7") (pin "2") (pinfunction "A1_2") (pintype "bidirectional"))
    )
    (net (code "78") (name "Net-(U7-A2)") (class "Default")
      (node (ref "C47") (pin "1") (pintype "passive"))
      (node (ref "R58") (pin "1") (pinfunction "1_1") (pintype "passive"))
      (node (ref "U7") (pin "3") (pinfunction "A2_3") (pintype "bidirectional"))
    )
    (net (code "79") (name "Net-(U7-A3)") (class "Default")
      (node (ref "C48") (pin "1") (pintype "passive"))
      (node (ref "R60") (pin "1") (pinfunction "1_1") (pintype "passive"))
      (node (ref "U7") (pin "4") (pinfunction "A3_4") (pintype "bidirectional"))
    )
    (net (code "80") (name "Net-(U7-A4)") (class "Default")
      (node (ref "C49") (pin "1") (pintype "passive"))
      (node (ref "R62") (pin "1") (pinfunction "1_1") (pintype "passive"))
      (node (ref "U7") (pin "5") (pinfunction "A4_5") (pintype "bidirectional"))
    )
    (net (code "81") (name "Net-(U7-A5)") (class "Default")
      (node (ref "C50") (pin "1") (pintype "passive"))
      (node (ref "R64") (pin "1") (pinfunction "1_1") (pintype "passive"))
      (node (ref "U7") (pin "6") (pinfunction "A5_6") (pintype "bidirectional"))
    )
    (net (code "82") (name "Net-(U7-A6)") (class "Default")
      (node (ref "C51") (pin "1") (pintype "passive"))
      (node (ref "R66") (pin "1") (pinfunction "1_1") (pintype "passive"))
      (node (ref "U7") (pin "7") (pinfunction "A6_7") (pintype "bidirectional"))
    )
    (net (code "83") (name "Net-(U7-A7)") (class "Default")
      (node (ref "C52") (pin "1") (pintype "passive"))
      (node (ref "R70") (pin "1") (pinfunction "1_1") (pintype "passive"))
      (node (ref "U7") (pin "8") (pinfunction "A7_8") (pintype "bidirectional"))
    )
    (net (code "84") (name "Net-(U7-A8)") (class "Default")
      (node (ref "C53") (pin "1") (pintype "passive"))
      (node (ref "R72") (pin "1") (pinfunction "1_1") (pintype "passive"))
      (node (ref "U7") (pin "9") (pinfunction "A8_9") (pintype "bidirectional"))
    )
    (net (code "85") (name "Net-(U7-B1)") (class "Default")
      (node (ref "R55") (pin "2") (pinfunction "2_2") (pintype "passive"))
      (node (ref "U7") (pin "18") (pinfunction "B1_18") (pintype "bidirectional"))
    )
    (net (code "86") (name "Net-(U7-B2)") (class "Default")
      (node (ref "R57") (pin "2") (pinfunction "2_2") (pintype "passive"))
      (node (ref "U7") (pin "17") (pinfunction "B2_17") (pintype "bidirectional"))
    )
    (net (code "87") (name "Net-(U7-B3)") (class "Default")
      (node (ref "R59") (pin "2") (pinfunction "2_2") (pintype "passive"))
      (node (ref "U7") (pin "16") (pinfunction "B3_16") (pintype "bidirectional"))
    )
    (net (code "88") (name "Net-(U7-B4)") (class "Default")
      (node (ref "R61") (pin "2") (pinfunction "2_2") (pintype "passive"))
      (node (ref "U7") (pin "15") (pinfunction "B4_15") (pintype "bidirectional"))
    )
    (net (code "89") (name "Net-(U7-B5)") (class "Default")
      (node (ref "R63") (pin "2") (pinfunction "2_2") (pintype "passive"))
      (node (ref "U7") (pin "14") (pinfunction "B5_14") (pintype "bidirectional"))
    )
    (net (code "90") (name "Net-(U7-B6)") (class "Default")
      (node (ref "R65") (pin "2") (pinfunction "2_2") (pintype "passive"))
      (node (ref "U7") (pin "13") (pinfunction "B6_13") (pintype "bidirectional"))
    )
    (net (code "91") (name "Net-(U7-B7)") (class "Default")
      (node (ref "R69") (pin "2") (pinfunction "2_2") (pintype "passive"))
      (node (ref "U7") (pin "12") (pinfunction "B7_12") (pintype "bidirectional"))
    )
    (net (code "92") (name "Net-(U7-B8)") (class "Default")
      (node (ref "R71") (pin "2") (pinfunction "2_2") (pintype "passive"))
      (node (ref "U7") (pin "11") (pinfunction "B8_11") (pintype "bidirectional"))
    )
    (net (code "93") (name "Net-(U7-DIR)") (class "Default")
      (node (ref "R76") (pin "2") (pinfunction "2_2") (pintype "passive"))
      (node (ref "R80") (pin "1") (pinfunction "1_1") (pintype "passive"))
      (node (ref "U7") (pin "1") (pinfunction "DIR_1") (pintype "input"))
    )
    (net (code "94") (name "Net-(U7-VCC)") (class "Default")
      (node (ref "C44") (pin "2") (pintype "passive"))
      (node (ref "R53") (pin "2") (pinfunction "2_2") (pintype "passive"))
      (node (ref "R54") (pin "2") (pinfunction "2_2") (pintype "passive"))
      (node (ref "U7") (pin "20") (pinfunction "VCC_20") (pintype "power_in"))
    )
    (net (code "95") (name "Net-(U8-A)") (class "Default")
      (node (ref "C54") (pin "1") (pintype "passive"))
      (node (ref "P7") (pin "1") (pinfunction "1_1") (pintype "passive"))
      (node (ref "R73") (pin "2") (pinfunction "2_2") (pintype "passive"))
      (node (ref "R75") (pin "1") (pinfunction "1_1") (pintype "passive"))
      (node (ref "U8") (pin "6") (pinfunction "A_6") (pintype "bidirectional"))
    )
    (net (code "96") (name "Net-(U8-B)") (class "Default")
      (node (ref "C55") (pin "1") (pintype "passive"))
      (node (ref "P7") (pin "2") (pinfunction "2_2") (pintype "passive"))
      (node (ref "R75") (pin "2") (pinfunction "2_2") (pintype "passive"))
      (node (ref "R79") (pin "1") (pinfunction "1_1") (pintype "passive"))
      (node (ref "U8") (pin "7") (pinfunction "B_7") (pintype "bidirectional"))
    )
    (net (code "97") (name "Net-(U8-DE)") (class "Default")
      (node (ref "R77") (pin "1") (pinfunction "1_1") (pintype "passive"))
      (node (ref "U8") (pin "2") (pinfunction "~{RE}_2") (pintype "output"))
      (node (ref "U8") (pin "3") (pinfunction "DE_3") (pintype "input"))
    )
    (net (code "98") (name "Net-(U8-DI)") (class "Default")
      (node (ref "R78") (pin "1") (pinfunction "1_1") (pintype "passive"))
      (node (ref "U8") (pin "4") (pinfunction "DI_4") (pintype "input"))
    )
    (net (code "99") (name "Net-(U8-RO)") (class "Default")
      (node (ref "R74") (pin "1") (pinfunction "1_1") (pintype "passive"))
      (node (ref "U8") (pin "1") (pinfunction "RO_1") (pintype "output"))
    )
  )
)
